# HL_gas_no2_pcb.net
KiCad netlist of a schematic drawn in EAGLE
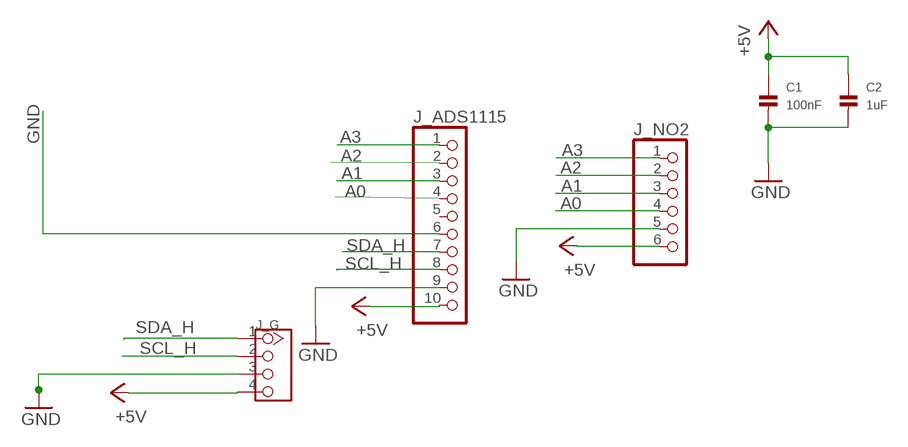
[diagram p0: schematic, sheet 1]

(export (version "E")
  (design (tool "Eeschema 10.0.6"))
  (components
    (comp (ref "C1")
      (value "100nF")
      (footprint "eagle-import:1206")
      (libsource (lib "eagle-import") (part "CAP_CERAMIC1206"))
    )
    (comp (ref "C2")
      (value "1uF")
      (footprint "eagle-import:1206")
      (libsource (lib "eagle-import") (part "CAP_CERAMIC1206"))
    )
    (comp (ref "J_ADS1115")
      (value "HEADER-1X10")
      (footprint "eagle-import:1X10_OVAL")
      (libsource (lib "eagle-import") (part "HEADER-1X10"))
    )
    (comp (ref "J_G")
      (value "TWIG-4P-2.0-2.0")
      (footprint "eagle-import:4P-2.0")
      (libsource (lib "eagle-import") (part "TWIG-4P-2.0-2.0"))
    )
    (comp (ref "J_NO2")
      (value "HEADER-1X6")
      (footprint "eagle-import:1X06_OVAL")
      (libsource (lib "eagle-import") (part "HEADER-1X6"))
    )
  )
  (nets
    (net (code "1") (name "+5V") (class "Default")
      (node (ref "C1") (pin "1") (pinfunction "P$1_1") (pintype "passive"))
      (node (ref "C2") (pin "1") (pinfunction "P$1_1") (pintype "passive"))
      (node (ref "J_ADS1115") (pin "10") (pinfunction "10_10") (pintype "passive"))
      (node (ref "J_G") (pin "4") (pinfunction "4_4") (pintype "bidirectional"))
      (node (ref "J_NO2") (pin "6") (pinfunction "6_6") (pintype "passive"))
    )
    (net (code "2") (name "/A0") (class "Default")
      (node (ref "J_ADS1115") (pin "4") (pinfunction "4_4") (pintype "passive"))
      (node (ref "J_NO2") (pin "4") (pinfunction "4_4") (pintype "passive"))
    )
    (net (code "3") (name "/A1") (class "Default")
      (node (ref "J_ADS1115") (pin "3") (pinfunction "3_3") (pintype "passive"))
      (node (ref "J_NO2") (pin "3") (pinfunction "3_3") (pintype "passive"))
    )
    (net (code "4") (name "/A2") (class "Default")
      (node (ref "J_ADS1115") (pin "2") (pinfunction "2_2") (pintype "passive"))
      (node (ref "J_NO2") (pin "2") (pinfunction "2_2") (pintype "passive"))
    )
    (net (code "5") (name "/A3") (class "Default")
      (node (ref "J_ADS1115") (pin "1") (pinfunction "1_1") (pintype "passive"))
      (node (ref "J_NO2") (pin "1") (pinfunction "1_1") (pintype "passive"))
    )
    (net (code "6") (name "/SCL_H") (class "Default")
      (node (ref "J_ADS1115") (pin "8") (pinfunction "8_8") (pintype "passive"))
      (node (ref "J_G") (pin "2") (pinfunction "2_2") (pintype "bidirectional"))
    )
    (net (code "7") (name "/SDA_H") (class "Default")
      (node (ref "J_ADS1115") (pin "7") (pinfunction "7_7") (pintype "passive"))
      (node (ref "J_G") (pin "1") (pinfunction "1_1") (pintype "bidirectional"))
    )
    (net (code "8") (name "GND") (class "Default")
      (node (ref "C1") (pin "2") (pinfunction "P$2_2") (pintype "passive"))
      (node (ref "C2") (pin "2") (pinfunction "P$2_2") (pintype "passive"))
      (node (ref "J_ADS1115") (pin "6") (pinfunction "6_6") (pintype "passive"))
      (node (ref "J_ADS1115") (pin "9") (pinfunction "9_9") (pintype "passive"))
      (node (ref "J_G") (pin "3") (pinfunction "3_3") (pintype "bidirectional"))
      (node (ref "J_NO2") (pin "5") (pinfunction "5_5") (pintype "passive"))
    )
    (net (code "9") (name "unconnected-(J_ADS1115-Pad5)") (class "Default")
      (node (ref "J_ADS1115") (pin "5") (pinfunction "5_5") (pintype "passive"))
    )
  )
)
